# 4-20mA_Converter.net
KiCad netlist of a schematic drawn in Altium Designer
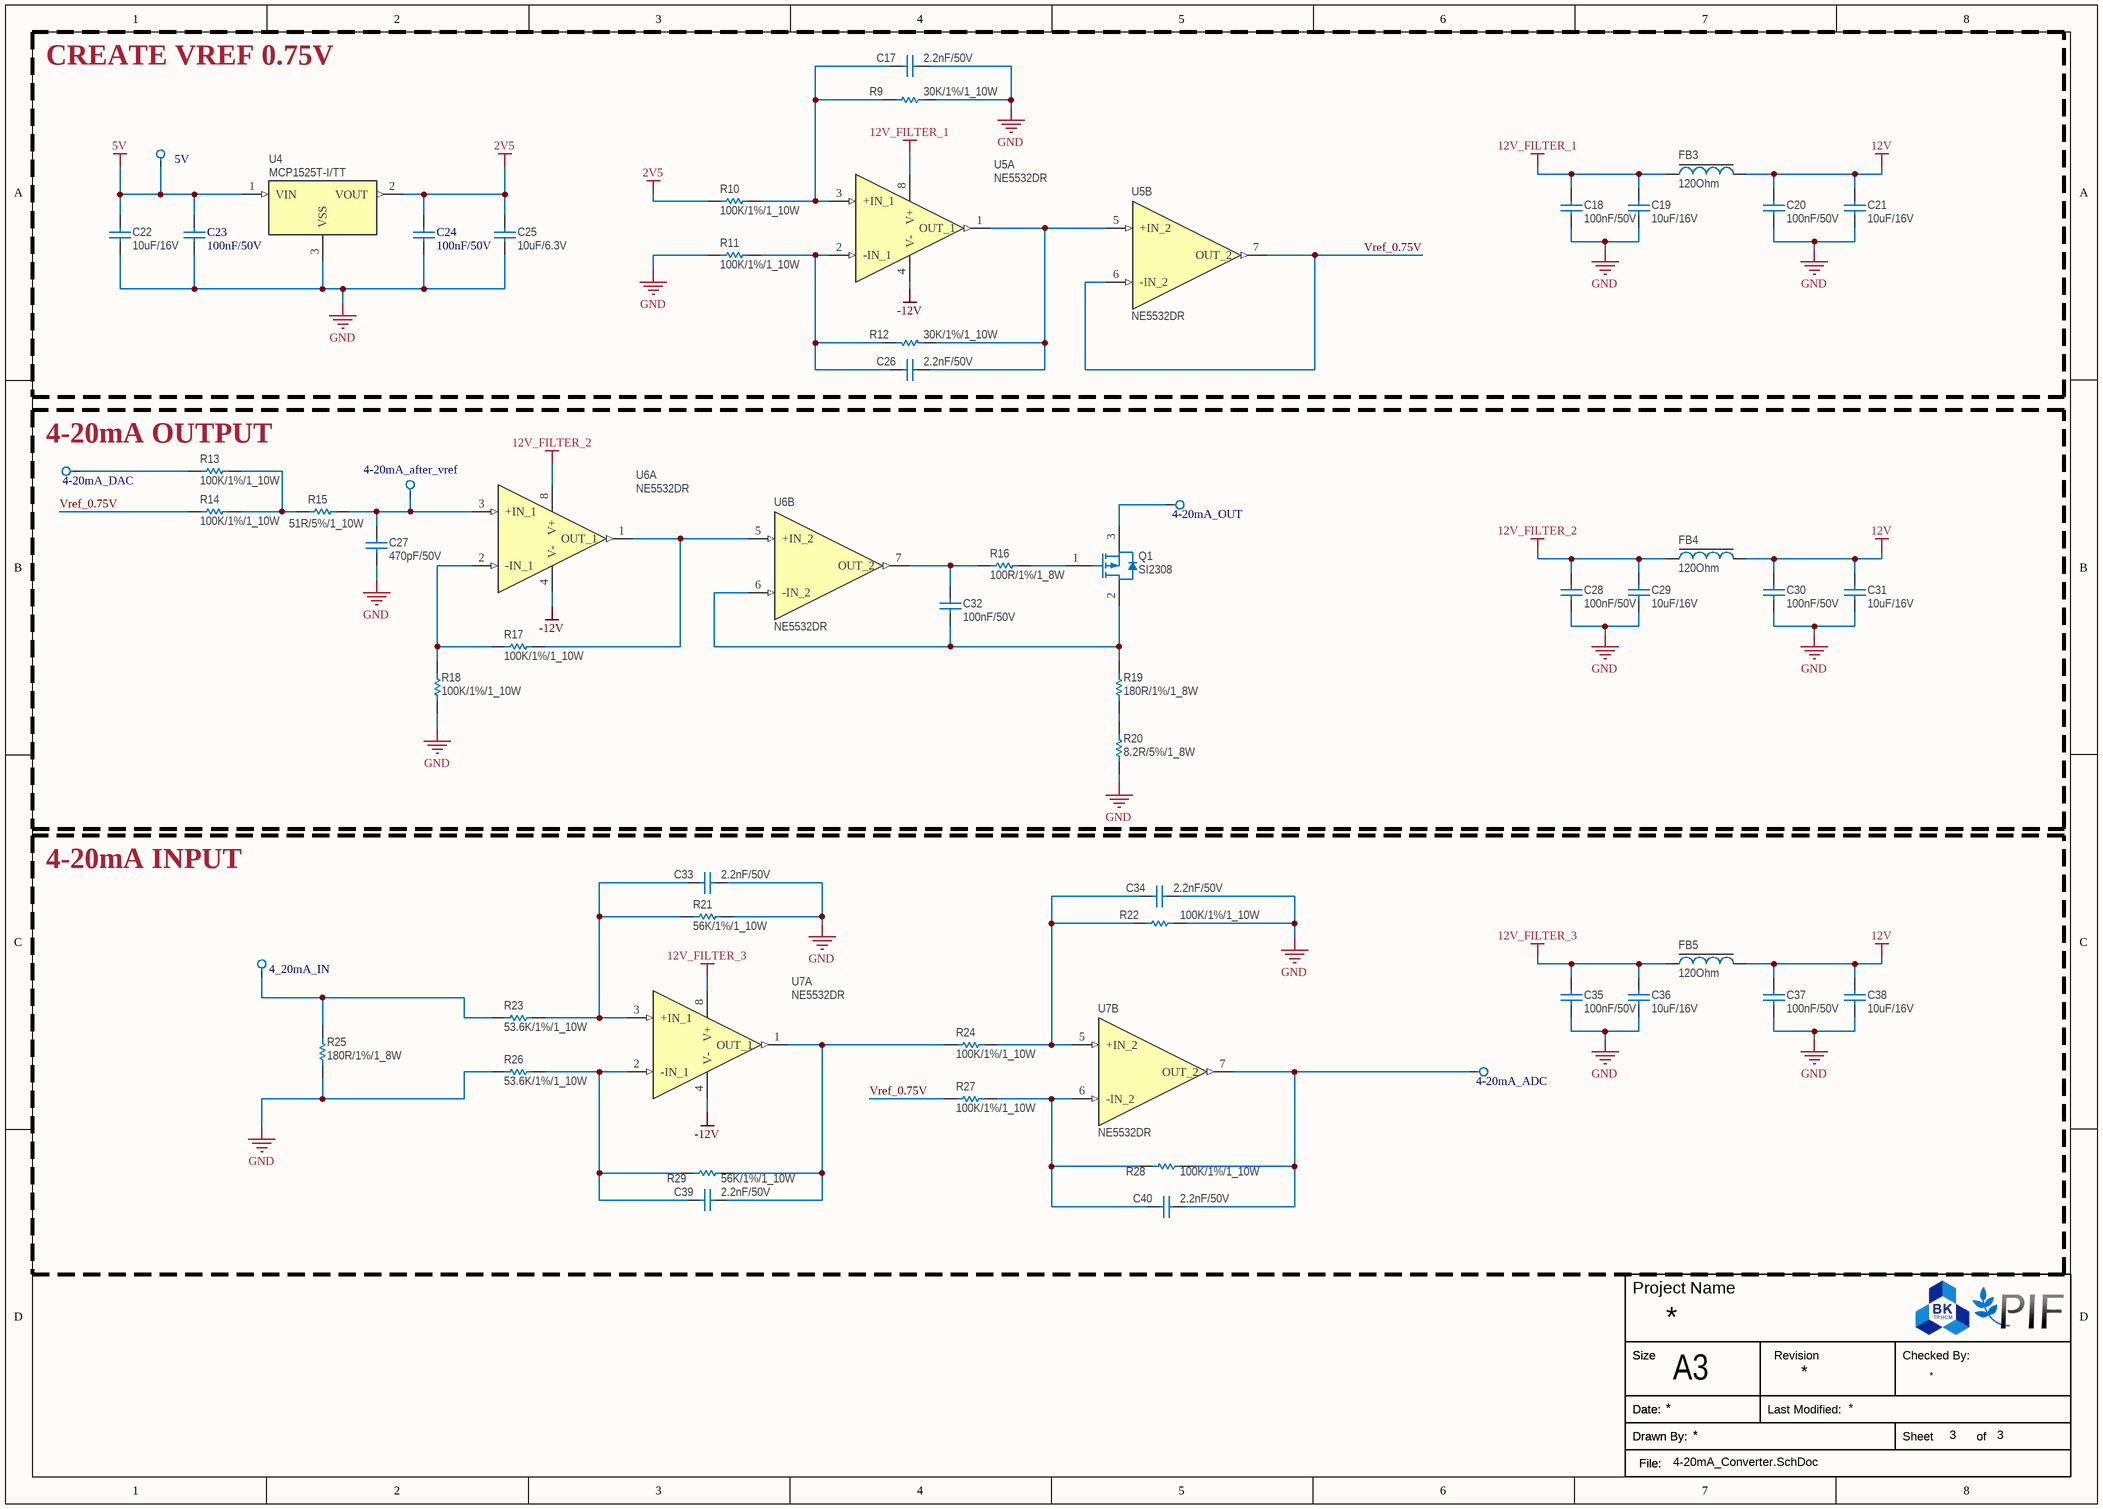
[diagram p0: 4-20mA_Converter.SchDoc]

(export (version "E")
  (design (tool "Eeschema 10.0.6"))
  (components
    (comp (ref "4-20mA_ADC")
      (value "4-20mA_ADC")
      (footprint "TestPoint_THTPad_D1.5mm_Drill0.7mm")
      (description "Test Point TEST-1BK")
      (libsource (lib "BluetoothTracking") (part "Testpoint_TH"))
    )
    (comp (ref "4-20mA_after_vref")
      (value "4-20mA_after_vref")
      (footprint "TestPoint_THTPad_D1.5mm_Drill0.7mm")
      (description "Test Point TEST-1BK")
      (libsource (lib "BluetoothTracking") (part "Testpoint_TH"))
    )
    (comp (ref "4-20mA_DAC")
      (value "4-20mA_DAC")
      (footprint "TestPoint_THTPad_D1.5mm_Drill0.7mm")
      (description "Test Point TEST-1BK")
      (libsource (lib "BluetoothTracking") (part "Testpoint_TH"))
    )
    (comp (ref "4-20mA_OUT")
      (value "4-20mA_OUT")
      (footprint "TestPoint_THTPad_D1.5mm_Drill0.7mm")
      (description "Test Point TEST-1BK")
      (libsource (lib "BluetoothTracking") (part "Testpoint_TH"))
    )
    (comp (ref "4_20mA_IN")
      (value "4_20mA_IN")
      (footprint "TestPoint_THTPad_D1.5mm_Drill0.7mm")
      (description "Test Point TEST-1BK")
      (libsource (lib "BluetoothTracking") (part "Testpoint_TH"))
    )
    (comp (ref "5V")
      (value "Testpoint_SMD")
      (footprint "TestPoint_Pad_3.0x3.0mm")
      (libsource (lib "BluetoothTracking") (part "Testpoint_SMD"))
    )
    (comp (ref "C17")
      (value "2.2nF/50V")
      (footprint "CAP_0603")
      (description "CAP, size 0603, 2.2nF, 50V")
      (fields (field (name "SUPPLY PART NUMBER") "CC0603KRX7R9BB222"))
      (libsource (lib "BluetoothTracking") (part "Ceramic_Cap_2.2nF_50V_0603"))
    )
    (comp (ref "C18")
      (value "100nF/50V")
      (footprint "CAP_0603")
      (description "CAP, size 0603, 100nF, 50V")
      (fields (field (name "SUPPLY PART NUMBER") "Tụ Gốm 0603 100nF (0.1uF) 50V"))
      (libsource (lib "BluetoothTracking") (part "Ceramic_Cap_100nF_50V_0603"))
    )
    (comp (ref "C19")
      (value "10uF/16V")
      (footprint "CAP_0603")
      (description "CAP, size 0603, 10uF, 16V")
      (fields (field (name "SUPPLY PART NUMBER") "Tụ Gốm 0603 10uF 16V"))
      (libsource (lib "BluetoothTracking") (part "Ceramic_Cap_10uF_16V_0603"))
    )
    (comp (ref "C20")
      (value "100nF/50V")
      (footprint "CAP_0603")
      (description "CAP, size 0603, 100nF, 50V")
      (fields (field (name "SUPPLY PART NUMBER") "Tụ Gốm 0603 100nF (0.1uF) 50V"))
      (libsource (lib "BluetoothTracking") (part "Ceramic_Cap_100nF_50V_0603"))
    )
    (comp (ref "C21")
      (value "10uF/16V")
      (footprint "CAP_0603")
      (description "CAP, size 0603, 10uF, 16V")
      (fields (field (name "SUPPLY PART NUMBER") "Tụ Gốm 0603 10uF 16V"))
      (libsource (lib "BluetoothTracking") (part "Ceramic_Cap_10uF_16V_0603"))
    )
    (comp (ref "C22")
      (value "10uF/16V")
      (footprint "CAP_0603")
      (description "CAP, size 0603, 10uF, 16V")
      (fields (field (name "SUPPLY PART NUMBER") "Tụ Gốm 0603 10uF 16V"))
      (libsource (lib "BluetoothTracking") (part "Ceramic_Cap_10uF_16V_0603"))
    )
    (comp (ref "C23")
      (value "100nF/50V")
      (footprint "CAP_0603")
      (description "CAP, size 0603, 100nF, 50V")
      (fields (field (name "SUPPLY PART NUMBER") "Tụ Gốm 0603 100nF (0.1uF) 50V"))
      (libsource (lib "BluetoothTracking") (part "Ceramic_Cap_100nF_50V_0603"))
    )
    (comp (ref "C24")
      (value "100nF/50V")
      (footprint "CAP_0603")
      (description "CAP, size 0603, 100nF, 50V")
      (fields (field (name "SUPPLY PART NUMBER") "Tụ Gốm 0603 100nF (0.1uF) 50V"))
      (libsource (lib "BluetoothTracking") (part "Ceramic_Cap_100nF_50V_0603"))
    )
    (comp (ref "C25")
      (value "10uF/6.3V")
      (footprint "CAP_0603")
      (description "CAP, size 0603, 10uF, 6.3V")
      (fields (field (name "SUPPLY PART NUMBER") "CC0603KRX5R5BB106"))
      (libsource (lib "BluetoothTracking") (part "Ceramic_Cap_10uF_6.3V_0603"))
    )
    (comp (ref "C26")
      (value "2.2nF/50V")
      (footprint "CAP_0603")
      (description "CAP, size 0603, 2.2nF, 50V")
      (fields (field (name "SUPPLY PART NUMBER") "CC0603KRX7R9BB222"))
      (libsource (lib "BluetoothTracking") (part "Ceramic_Cap_2.2nF_50V_0603"))
    )
    (comp (ref "C27")
      (value "470pF/50V")
      (footprint "CAP_0603")
      (description "CAP, size 0603, 470pF, 50V")
      (fields (field (name "SUPPLY PART NUMBER") "Tụ Gốm 0603 470pF 50V"))
      (libsource (lib "BluetoothTracking") (part "Ceramic_Cap_470pF_50V_0603"))
    )
    (comp (ref "C28")
      (value "100nF/50V")
      (footprint "CAP_0603")
      (description "CAP, size 0603, 100nF, 50V")
      (fields (field (name "SUPPLY PART NUMBER") "Tụ Gốm 0603 100nF (0.1uF) 50V"))
      (libsource (lib "BluetoothTracking") (part "Ceramic_Cap_100nF_50V_0603"))
    )
    (comp (ref "C29")
      (value "10uF/16V")
      (footprint "CAP_0603")
      (description "CAP, size 0603, 10uF, 16V")
      (fields (field (name "SUPPLY PART NUMBER") "Tụ Gốm 0603 10uF 16V"))
      (libsource (lib "BluetoothTracking") (part "Ceramic_Cap_10uF_16V_0603"))
    )
    (comp (ref "C30")
      (value "100nF/50V")
      (footprint "CAP_0603")
      (description "CAP, size 0603, 100nF, 50V")
      (fields (field (name "SUPPLY PART NUMBER") "Tụ Gốm 0603 100nF (0.1uF) 50V"))
      (libsource (lib "BluetoothTracking") (part "Ceramic_Cap_100nF_50V_0603"))
    )
    (comp (ref "C31")
      (value "10uF/16V")
      (footprint "CAP_0603")
      (description "CAP, size 0603, 10uF, 16V")
      (fields (field (name "SUPPLY PART NUMBER") "Tụ Gốm 0603 10uF 16V"))
      (libsource (lib "BluetoothTracking") (part "Ceramic_Cap_10uF_16V_0603"))
    )
    (comp (ref "C32")
      (value "100nF/50V")
      (footprint "CAP_0603")
      (description "CAP, size 0603, 100nF, 50V")
      (fields (field (name "SUPPLY PART NUMBER") "Tụ Gốm 0603 100nF (0.1uF) 50V"))
      (libsource (lib "BluetoothTracking") (part "Ceramic_Cap_100nF_50V_0603"))
    )
    (comp (ref "C33")
      (value "2.2nF/50V")
      (footprint "CAP_0603")
      (description "CAP, size 0603, 2.2nF, 50V")
      (fields (field (name "SUPPLY PART NUMBER") "CC0603KRX7R9BB222"))
      (libsource (lib "BluetoothTracking") (part "Ceramic_Cap_2.2nF_50V_0603"))
    )
    (comp (ref "C34")
      (value "2.2nF/50V")
      (footprint "CAP_0603")
      (description "CAP, size 0603, 2.2nF, 50V")
      (fields (field (name "SUPPLY PART NUMBER") "CC0603KRX7R9BB222"))
      (libsource (lib "BluetoothTracking") (part "Ceramic_Cap_2.2nF_50V_0603"))
    )
    (comp (ref "C35")
      (value "100nF/50V")
      (footprint "CAP_0603")
      (description "CAP, size 0603, 100nF, 50V")
      (fields (field (name "SUPPLY PART NUMBER") "Tụ Gốm 0603 100nF (0.1uF) 50V"))
      (libsource (lib "BluetoothTracking") (part "Ceramic_Cap_100nF_50V_0603"))
    )
    (comp (ref "C36")
      (value "10uF/16V")
      (footprint "CAP_0603")
      (description "CAP, size 0603, 10uF, 16V")
      (fields (field (name "SUPPLY PART NUMBER") "Tụ Gốm 0603 10uF 16V"))
      (libsource (lib "BluetoothTracking") (part "Ceramic_Cap_10uF_16V_0603"))
    )
    (comp (ref "C37")
      (value "100nF/50V")
      (footprint "CAP_0603")
      (description "CAP, size 0603, 100nF, 50V")
      (fields (field (name "SUPPLY PART NUMBER") "Tụ Gốm 0603 100nF (0.1uF) 50V"))
      (libsource (lib "BluetoothTracking") (part "Ceramic_Cap_100nF_50V_0603"))
    )
    (comp (ref "C38")
      (value "10uF/16V")
      (footprint "CAP_0603")
      (description "CAP, size 0603, 10uF, 16V")
      (fields (field (name "SUPPLY PART NUMBER") "Tụ Gốm 0603 10uF 16V"))
      (libsource (lib "BluetoothTracking") (part "Ceramic_Cap_10uF_16V_0603"))
    )
    (comp (ref "C39")
      (value "2.2nF/50V")
      (footprint "CAP_0603")
      (description "CAP, size 0603, 2.2nF, 50V")
      (fields (field (name "SUPPLY PART NUMBER") "CC0603KRX7R9BB222"))
      (libsource (lib "BluetoothTracking") (part "Ceramic_Cap_2.2nF_50V_0603"))
    )
    (comp (ref "C40")
      (value "2.2nF/50V")
      (footprint "CAP_0603")
      (description "CAP, size 0603, 2.2nF, 50V")
      (fields (field (name "SUPPLY PART NUMBER") "CC0603KRX7R9BB222"))
      (libsource (lib "BluetoothTracking") (part "Ceramic_Cap_2.2nF_50V_0603"))
    )
    (comp (ref "FB3")
      (value "120Ohm")
      (footprint "Ferrite_Bead_0805")
      (description "Ferrite Bead, size 0805, 120Ohm, 2A")
      (fields (field (name "SUPPLY PART NUMBER") "CBW201209U121T Ferrite Beads 2A 120 Ohm 0805"))
      (libsource (lib "BluetoothTracking") (part "Ferrite_Bead_120Ohm_2A_0805"))
    )
    (comp (ref "FB4")
      (value "120Ohm")
      (footprint "Ferrite_Bead_0805")
      (description "Ferrite Bead, size 0805, 120Ohm, 2A")
      (fields (field (name "SUPPLY PART NUMBER") "CBW201209U121T Ferrite Beads 2A 120 Ohm 0805"))
      (libsource (lib "BluetoothTracking") (part "Ferrite_Bead_120Ohm_2A_0805"))
    )
    (comp (ref "FB5")
      (value "120Ohm")
      (footprint "Ferrite_Bead_0805")
      (description "Ferrite Bead, size 0805, 120Ohm, 2A")
      (fields (field (name "SUPPLY PART NUMBER") "CBW201209U121T Ferrite Beads 2A 120 Ohm 0805"))
      (libsource (lib "BluetoothTracking") (part "Ferrite_Bead_120Ohm_2A_0805"))
    )
    (comp (ref "Q1")
      (value "SI2308")
      (footprint "SOT-23")
      (description "SI2308 SOT23 MOSFET N-CH 2A 60V")
      (libsource (lib "BluetoothTracking") (part "SI2308"))
    )
    (comp (ref "R9")
      (value "30K/1%/1_10W")
      (footprint "Resistor_0603")
      (description "Resistor 0603 30KOhm 1% 1_10W")
      (fields (field (name "SUPPLY PART NUMBER") "Điện Trở 30 KOhm 0603 1%"))
      (libsource (lib "BluetoothTracking") (part "Res_30K_0603_1%"))
    )
    (comp (ref "R10")
      (value "100K/1%/1_10W")
      (footprint "Resistor_0603")
      (description "Resistor 0603 100KOhm 1% 1_10W")
      (fields (field (name "SUPPLY PART NUMBER") "Điện Trở 100 KOhm 0603 1%"))
      (libsource (lib "BluetoothTracking") (part "Res_100K_0603_1%"))
    )
    (comp (ref "R11")
      (value "100K/1%/1_10W")
      (footprint "Resistor_0603")
      (description "Resistor 0603 100KOhm 1% 1_10W")
      (fields (field (name "SUPPLY PART NUMBER") "Điện Trở 100 KOhm 0603 1%"))
      (libsource (lib "BluetoothTracking") (part "Res_100K_0603_1%"))
    )
    (comp (ref "R12")
      (value "30K/1%/1_10W")
      (footprint "Resistor_0603")
      (description "Resistor 0603 30KOhm 1% 1_10W")
      (fields (field (name "SUPPLY PART NUMBER") "Điện Trở 30 KOhm 0603 1%"))
      (libsource (lib "BluetoothTracking") (part "Res_30K_0603_1%"))
    )
    (comp (ref "R13")
      (value "100K/1%/1_10W")
      (footprint "Resistor_0603")
      (description "Resistor 0603 100KOhm 1% 1_10W")
      (fields (field (name "SUPPLY PART NUMBER") "Điện Trở 100 KOhm 0603 1%"))
      (libsource (lib "BluetoothTracking") (part "Res_100K_0603_1%"))
    )
    (comp (ref "R14")
      (value "100K/1%/1_10W")
      (footprint "Resistor_0603")
      (description "Resistor 0603 100KOhm 1% 1_10W")
      (fields (field (name "SUPPLY PART NUMBER") "Điện Trở 100 KOhm 0603 1%"))
      (libsource (lib "BluetoothTracking") (part "Res_100K_0603_1%"))
    )
    (comp (ref "R15")
      (value "51R/5%/1_10W")
      (footprint "Resistor_0603")
      (description "Resistor 0603 51 Ohm 5% 1_10W")
      (fields (field (name "SUPPLY PART NUMBER") "Điện Trở 51 Ohm 0603 5%"))
      (libsource (lib "BluetoothTracking") (part "Res_51R_0603_5%"))
    )
    (comp (ref "R16")
      (value "100R/1%/1_8W")
      (footprint "Resistor_0603")
      (description "Resistor 0805 100 Ohm 1% 1_8W")
      (fields (field (name "SUPPLY PART NUMBER") "Điện Trở 100 Ohm 0805 1%"))
      (libsource (lib "BluetoothTracking") (part "Res_100R_0805_1%"))
    )
    (comp (ref "R17")
      (value "100K/1%/1_10W")
      (footprint "Resistor_0603")
      (description "Resistor 0603 100KOhm 1% 1_10W")
      (fields (field (name "SUPPLY PART NUMBER") "Điện Trở 100 KOhm 0603 1%"))
      (libsource (lib "BluetoothTracking") (part "Res_100K_0603_1%"))
    )
    (comp (ref "R18")
      (value "100K/1%/1_10W")
      (footprint "Resistor_0603")
      (description "Resistor 0603 100KOhm 1% 1_10W")
      (fields (field (name "SUPPLY PART NUMBER") "Điện Trở 100 KOhm 0603 1%"))
      (libsource (lib "BluetoothTracking") (part "Res_100K_0603_1%"))
    )
    (comp (ref "R19")
      (value "180R/1%/1_8W")
      (footprint "Resistor_0805")
      (description "Resistor 0805 180 Ohm 1% 1_8W")
      (fields (field (name "SUPPLY PART NUMBER") "Điện Trở 180 Ohm 0805 1%"))
      (libsource (lib "BluetoothTracking") (part "Res_180R_0805_1%"))
    )
    (comp (ref "R20")
      (value "8.2R/5%/1_8W")
      (footprint "Resistor_0805")
      (description "Resistor 0805 8.2 Ohm 5% 1_8W")
      (fields (field (name "SUPPLY PART NUMBER") "Điện Trở 8.2 Ohm 0805 5%"))
      (libsource (lib "BluetoothTracking") (part "Res_8.2R_0805_5%"))
    )
    (comp (ref "R21")
      (value "56K/1%/1_10W")
      (footprint "Resistor_0603")
      (description "Resistor 0603 56KOhm 1% 1_10W")
      (fields (field (name "SUPPLY PART NUMBER") "Điện Trở 56 KOhm 0603 1%"))
      (libsource (lib "BluetoothTracking") (part "Res_56K_0603_1%"))
    )
    (comp (ref "R22")
      (value "100K/1%/1_10W")
      (footprint "Resistor_0603")
      (description "Resistor 0603 100KOhm 1% 1_10W")
      (fields (field (name "SUPPLY PART NUMBER") "Điện Trở 100 KOhm 0603 1%"))
      (libsource (lib "BluetoothTracking") (part "Res_100K_0603_1%"))
    )
    (comp (ref "R23")
      (value "53.6K/1%/1_10W")
      (footprint "Resistor_0603")
      (description "Resistor 0603 53.6KOhm 1% 1_10W")
      (fields (field (name "SUPPLY PART NUMBER") "Điện Trở 53.6 KOhm 0603 1%"))
      (libsource (lib "BluetoothTracking") (part "Res_53.6K_0603_1%"))
    )
    (comp (ref "R24")
      (value "100K/1%/1_10W")
      (footprint "Resistor_0603")
      (description "Resistor 0603 100KOhm 1% 1_10W")
      (fields (field (name "SUPPLY PART NUMBER") "Điện Trở 100 KOhm 0603 1%"))
      (libsource (lib "BluetoothTracking") (part "Res_100K_0603_1%"))
    )
    (comp (ref "R25")
      (value "180R/1%/1_8W")
      (footprint "Resistor_0805")
      (description "Resistor 0805 180 Ohm 1% 1_8W")
      (fields (field (name "SUPPLY PART NUMBER") "Điện Trở 180 Ohm 0805 1%"))
      (libsource (lib "BluetoothTracking") (part "Res_180R_0805_1%"))
    )
    (comp (ref "R26")
      (value "53.6K/1%/1_10W")
      (footprint "Resistor_0603")
      (description "Resistor 0603 53.6KOhm 1% 1_10W")
      (fields (field (name "SUPPLY PART NUMBER") "Điện Trở 53.6 KOhm 0603 1%"))
      (libsource (lib "BluetoothTracking") (part "Res_53.6K_0603_1%"))
    )
    (comp (ref "R27")
      (value "100K/1%/1_10W")
      (footprint "Resistor_0603")
      (description "Resistor 0603 100KOhm 1% 1_10W")
      (fields (field (name "SUPPLY PART NUMBER") "Điện Trở 100 KOhm 0603 1%"))
      (libsource (lib "BluetoothTracking") (part "Res_100K_0603_1%"))
    )
    (comp (ref "R28")
      (value "100K/1%/1_10W")
      (footprint "Resistor_0603")
      (description "Resistor 0603 100KOhm 1% 1_10W")
      (fields (field (name "SUPPLY PART NUMBER") "Điện Trở 100 KOhm 0603 1%"))
      (libsource (lib "BluetoothTracking") (part "Res_100K_0603_1%"))
    )
    (comp (ref "R29")
      (value "56K/1%/1_10W")
      (footprint "Resistor_0603")
      (description "Resistor 0603 56KOhm 1% 1_10W")
      (fields (field (name "SUPPLY PART NUMBER") "Điện Trở 56 KOhm 0603 1%"))
      (libsource (lib "BluetoothTracking") (part "Res_56K_0603_1%"))
    )
    (comp (ref "U4")
      (value "MCP1525T-I/TT")
      (footprint "SOT-23")
      (description "Voltage Reference IC 2.5V")
      (fields (field (name "SUPPLY PART NUMBER") "MCP1525T-I/TT IC Tham Chiếu Điện Áp 2.5V SOT-23"))
      (libsource (lib "BluetoothTracking") (part "MCP1525T-I/TT"))
    )
    (comp (ref "U5")
      (value "NE5532DR")
      (footprint "SOIC-8")
      (description "Low Noise Single/Dual Operational Amplifier - SOIC-8")
      (libsource (lib "BluetoothTracking") (part "NE5532DR"))
    )
    (comp (ref "U6")
      (value "NE5532DR")
      (footprint "SOIC-8")
      (description "Low Noise Single/Dual Operational Amplifier - SOIC-8")
      (libsource (lib "BluetoothTracking") (part "NE5532DR"))
    )
    (comp (ref "U7")
      (value "NE5532DR")
      (footprint "SOIC-8")
      (description "Low Noise Single/Dual Operational Amplifier - SOIC-8")
      (libsource (lib "BluetoothTracking") (part "NE5532DR"))
    )
  )
  (nets
    (net (code "1") (name "-12V") (class "Default")
      (node (ref "U5") (pin "4") (pinfunction "V-_4") (pintype "power_in"))
      (node (ref "U6") (pin "4") (pinfunction "V-_4") (pintype "power_in"))
      (node (ref "U7") (pin "4") (pinfunction "V-_4") (pintype "power_in"))
    )
    (net (code "2") (name "/Vref_0.75V") (class "Default")
      (node (ref "R14") (pin "1") (pinfunction "1_1") (pintype "passive"))
      (node (ref "R27") (pin "1") (pinfunction "1_1") (pintype "passive"))
      (node (ref "U5") (pin "6") (pinfunction "-IN_2_6") (pintype "input"))
      (node (ref "U5") (pin "7") (pinfunction "OUT_2_7") (pintype "output"))
    )
    (net (code "3") (name "2V5") (class "Default")
      (node (ref "C24") (pin "2") (pinfunction "2_2") (pintype "passive"))
      (node (ref "C25") (pin "2") (pinfunction "2_2") (pintype "passive"))
      (node (ref "R10") (pin "1") (pinfunction "1_1") (pintype "passive"))
      (node (ref "U4") (pin "2") (pinfunction "VOUT_2") (pintype "output"))
    )
    (net (code "4") (name "5V") (class "Default")
      (node (ref "5V") (pin "1") (pinfunction "1_1") (pintype "passive"))
      (node (ref "C22") (pin "2") (pinfunction "2_2") (pintype "passive"))
      (node (ref "C23") (pin "2") (pinfunction "2_2") (pintype "passive"))
      (node (ref "U4") (pin "1") (pinfunction "VIN_1") (pintype "input"))
    )
    (net (code "5") (name "12V") (class "Default")
      (node (ref "C20") (pin "2") (pinfunction "2_2") (pintype "passive"))
      (node (ref "C21") (pin "2") (pinfunction "2_2") (pintype "passive"))
      (node (ref "C30") (pin "2") (pinfunction "2_2") (pintype "passive"))
      (node (ref "C31") (pin "2") (pinfunction "2_2") (pintype "passive"))
      (node (ref "C37") (pin "2") (pinfunction "2_2") (pintype "passive"))
      (node (ref "C38") (pin "2") (pinfunction "2_2") (pintype "passive"))
      (node (ref "FB3") (pin "2") (pinfunction "2_2") (pintype "passive"))
      (node (ref "FB4") (pin "2") (pinfunction "2_2") (pintype "passive"))
      (node (ref "FB5") (pin "2") (pinfunction "2_2") (pintype "passive"))
    )
    (net (code "6") (name "12V_FILTER_1") (class "Default")
      (node (ref "C18") (pin "2") (pinfunction "2_2") (pintype "passive"))
      (node (ref "C19") (pin "2") (pinfunction "2_2") (pintype "passive"))
      (node (ref "FB3") (pin "1") (pinfunction "1_1") (pintype "passive"))
      (node (ref "U5") (pin "8") (pinfunction "V+_8") (pintype "power_in"))
    )
    (net (code "7") (name "12V_FILTER_2") (class "Default")
      (node (ref "C28") (pin "2") (pinfunction "2_2") (pintype "passive"))
      (node (ref "C29") (pin "2") (pinfunction "2_2") (pintype "passive"))
      (node (ref "FB4") (pin "1") (pinfunction "1_1") (pintype "passive"))
      (node (ref "U6") (pin "8") (pinfunction "V+_8") (pintype "power_in"))
    )
    (net (code "8") (name "12V_FILTER_3") (class "Default")
      (node (ref "C35") (pin "2") (pinfunction "2_2") (pintype "passive"))
      (node (ref "C36") (pin "2") (pinfunction "2_2") (pintype "passive"))
      (node (ref "FB5") (pin "1") (pinfunction "1_1") (pintype "passive"))
      (node (ref "U7") (pin "8") (pinfunction "V+_8") (pintype "power_in"))
    )
    (net (code "9") (name "GND") (class "Default")
      (node (ref "C17") (pin "2") (pinfunction "2_2") (pintype "passive"))
      (node (ref "C18") (pin "1") (pinfunction "1_1") (pintype "passive"))
      (node (ref "C19") (pin "1") (pinfunction "1_1") (pintype "passive"))
      (node (ref "C20") (pin "1") (pinfunction "1_1") (pintype "passive"))
      (node (ref "C21") (pin "1") (pinfunction "1_1") (pintype "passive"))
      (node (ref "C22") (pin "1") (pinfunction "1_1") (pintype "passive"))
      (node (ref "C23") (pin "1") (pinfunction "1_1") (pintype "passive"))
      (node (ref "C24") (pin "1") (pinfunction "1_1") (pintype "passive"))
      (node (ref "C25") (pin "1") (pinfunction "1_1") (pintype "passive"))
      (node (ref "C27") (pin "1") (pinfunction "1_1") (pintype "passive"))
      (node (ref "C28") (pin "1") (pinfunction "1_1") (pintype "passive"))
      (node (ref "C29") (pin "1") (pinfunction "1_1") (pintype "passive"))
      (node (ref "C30") (pin "1") (pinfunction "1_1") (pintype "passive"))
      (node (ref "C31") (pin "1") (pinfunction "1_1") (pintype "passive"))
      (node (ref "C33") (pin "2") (pinfunction "2_2") (pintype "passive"))
      (node (ref "C34") (pin "2") (pinfunction "2_2") (pintype "passive"))
      (node (ref "C35") (pin "1") (pinfunction "1_1") (pintype "passive"))
      (node (ref "C36") (pin "1") (pinfunction "1_1") (pintype "passive"))
      (node (ref "C37") (pin "1") (pinfunction "1_1") (pintype "passive"))
      (node (ref "C38") (pin "1") (pinfunction "1_1") (pintype "passive"))
      (node (ref "R11") (pin "1") (pinfunction "1_1") (pintype "passive"))
      (node (ref "R18") (pin "1") (pinfunction "1_1") (pintype "passive"))
      (node (ref "R20") (pin "2") (pinfunction "2_2") (pintype "passive"))
      (node (ref "R21") (pin "2") (pinfunction "2_2") (pintype "passive"))
      (node (ref "R22") (pin "2") (pinfunction "2_2") (pintype "passive"))
      (node (ref "R25") (pin "1") (pinfunction "1_1") (pintype "passive"))
      (node (ref "R26") (pin "1") (pinfunction "1_1") (pintype "passive"))
      (node (ref "R9") (pin "2") (pinfunction "2_2") (pintype "passive"))
      (node (ref "U4") (pin "3") (pinfunction "VSS_3") (pintype "passive"))
    )
    (net (code "10") (name "Net-(4-20mA_DAC-Pad1)") (class "Default")
      (node (ref "4-20mA_DAC") (pin "1") (pinfunction "1_1") (pintype "passive"))
      (node (ref "R13") (pin "1") (pinfunction "1_1") (pintype "passive"))
    )
    (net (code "11") (name "Net-(4_20mA_IN-Pad1)") (class "Default")
      (node (ref "4_20mA_IN") (pin "1") (pinfunction "1_1") (pintype "passive"))
      (node (ref "R23") (pin "1") (pinfunction "1_1") (pintype "passive"))
      (node (ref "R25") (pin "2") (pinfunction "2_2") (pintype "passive"))
    )
    (net (code "12") (name "Net-(Q1-DRAIN)") (class "Default")
      (node (ref "4-20mA_OUT") (pin "1") (pinfunction "1_1") (pintype "passive"))
      (node (ref "Q1") (pin "3") (pinfunction "DRAIN_3") (pintype "passive"))
    )
    (net (code "13") (name "Net-(Q1-GATE)") (class "Default")
      (node (ref "Q1") (pin "1") (pinfunction "GATE_1") (pintype "passive"))
      (node (ref "R16") (pin "2") (pinfunction "2_2") (pintype "passive"))
    )
    (net (code "14") (name "Net-(Q1-SOURCE)") (class "Default")
      (node (ref "C32") (pin "1") (pinfunction "1_1") (pintype "passive"))
      (node (ref "Q1") (pin "2") (pinfunction "SOURCE_2") (pintype "passive"))
      (node (ref "R19") (pin "2") (pinfunction "2_2") (pintype "passive"))
      (node (ref "U6") (pin "6") (pinfunction "-IN_2_6") (pintype "input"))
    )
    (net (code "15") (name "Net-(R13-Pad2)") (class "Default")
      (node (ref "R13") (pin "2") (pinfunction "2_2") (pintype "passive"))
      (node (ref "R14") (pin "2") (pinfunction "2_2") (pintype "passive"))
      (node (ref "R15") (pin "1") (pinfunction "1_1") (pintype "passive"))
    )
    (net (code "16") (name "Net-(R19-Pad1)") (class "Default")
      (node (ref "R19") (pin "1") (pinfunction "1_1") (pintype "passive"))
      (node (ref "R20") (pin "1") (pinfunction "1_1") (pintype "passive"))
    )
    (net (code "17") (name "Net-(U5A-+IN_1)") (class "Default")
      (node (ref "C17") (pin "1") (pinfunction "1_1") (pintype "passive"))
      (node (ref "R10") (pin "2") (pinfunction "2_2") (pintype "passive"))
      (node (ref "R9") (pin "1") (pinfunction "1_1") (pintype "passive"))
      (node (ref "U5") (pin "3") (pinfunction "+IN_1_3") (pintype "input"))
    )
    (net (code "18") (name "Net-(U5A--IN_1)") (class "Default")
      (node (ref "C26") (pin "1") (pinfunction "1_1") (pintype "passive"))
      (node (ref "R11") (pin "2") (pinfunction "2_2") (pintype "passive"))
      (node (ref "R12") (pin "1") (pinfunction "1_1") (pintype "passive"))
      (node (ref "U5") (pin "2") (pinfunction "-IN_1_2") (pintype "input"))
    )
    (net (code "19") (name "Net-(U5A-OUT_1)") (class "Default")
      (node (ref "C26") (pin "2") (pinfunction "2_2") (pintype "passive"))
      (node (ref "R12") (pin "2") (pinfunction "2_2") (pintype "passive"))
      (node (ref "U5") (pin "1") (pinfunction "OUT_1_1") (pintype "output"))
      (node (ref "U5") (pin "5") (pinfunction "+IN_2_5") (pintype "input"))
    )
    (net (code "20") (name "Net-(U6A-+IN_1)") (class "Default")
      (node (ref "4-20mA_after_vref") (pin "1") (pinfunction "1_1") (pintype "passive"))
      (node (ref "C27") (pin "2") (pinfunction "2_2") (pintype "passive"))
      (node (ref "R15") (pin "2") (pinfunction "2_2") (pintype "passive"))
      (node (ref "U6") (pin "3") (pinfunction "+IN_1_3") (pintype "input"))
    )
    (net (code "21") (name "Net-(U6A--IN_1)") (class "Default")
      (node (ref "R17") (pin "1") (pinfunction "1_1") (pintype "passive"))
      (node (ref "R18") (pin "2") (pinfunction "2_2") (pintype "passive"))
      (node (ref "U6") (pin "2") (pinfunction "-IN_1_2") (pintype "input"))
    )
    (net (code "22") (name "Net-(U6A-OUT_1)") (class "Default")
      (node (ref "R17") (pin "2") (pinfunction "2_2") (pintype "passive"))
      (node (ref "U6") (pin "1") (pinfunction "OUT_1_1") (pintype "output"))
      (node (ref "U6") (pin "5") (pinfunction "+IN_2_5") (pintype "input"))
    )
    (net (code "23") (name "Net-(U6B-OUT_2)") (class "Default")
      (node (ref "C32") (pin "2") (pinfunction "2_2") (pintype "passive"))
      (node (ref "R16") (pin "1") (pinfunction "1_1") (pintype "passive"))
      (node (ref "U6") (pin "7") (pinfunction "OUT_2_7") (pintype "output"))
    )
    (net (code "24") (name "Net-(U7A-+IN_1)") (class "Default")
      (node (ref "C33") (pin "1") (pinfunction "1_1") (pintype "passive"))
      (node (ref "R21") (pin "1") (pinfunction "1_1") (pintype "passive"))
      (node (ref "R23") (pin "2") (pinfunction "2_2") (pintype "passive"))
      (node (ref "U7") (pin "3") (pinfunction "+IN_1_3") (pintype "input"))
    )
    (net (code "25") (name "Net-(U7A--IN_1)") (class "Default")
      (node (ref "C39") (pin "1") (pinfunction "1_1") (pintype "passive"))
      (node (ref "R26") (pin "2") (pinfunction "2_2") (pintype "passive"))
      (node (ref "R29") (pin "1") (pinfunction "1_1") (pintype "passive"))
      (node (ref "U7") (pin "2") (pinfunction "-IN_1_2") (pintype "input"))
    )
    (net (code "26") (name "Net-(U7A-OUT_1)") (class "Default")
      (node (ref "C39") (pin "2") (pinfunction "2_2") (pintype "passive"))
      (node (ref "R24") (pin "1") (pinfunction "1_1") (pintype "passive"))
      (node (ref "R29") (pin "2") (pinfunction "2_2") (pintype "passive"))
      (node (ref "U7") (pin "1") (pinfunction "OUT_1_1") (pintype "output"))
    )
    (net (code "27") (name "Net-(U7B-+IN_2)") (class "Default")
      (node (ref "C34") (pin "1") (pinfunction "1_1") (pintype "passive"))
      (node (ref "R22") (pin "1") (pinfunction "1_1") (pintype "passive"))
      (node (ref "R24") (pin "2") (pinfunction "2_2") (pintype "passive"))
      (node (ref "U7") (pin "5") (pinfunction "+IN_2_5") (pintype "input"))
    )
    (net (code "28") (name "Net-(U7B--IN_2)") (class "Default")
      (node (ref "C40") (pin "1") (pinfunction "1_1") (pintype "passive"))
      (node (ref "R27") (pin "2") (pinfunction "2_2") (pintype "passive"))
      (node (ref "R28") (pin "1") (pinfunction "1_1") (pintype "passive"))
      (node (ref "U7") (pin "6") (pinfunction "-IN_2_6") (pintype "input"))
    )
    (net (code "29") (name "Net-(U7B-OUT_2)") (class "Default")
      (node (ref "4-20mA_ADC") (pin "1") (pinfunction "1_1") (pintype "passive"))
      (node (ref "C40") (pin "2") (pinfunction "2_2") (pintype "passive"))
      (node (ref "R28") (pin "2") (pinfunction "2_2") (pintype "passive"))
      (node (ref "U7") (pin "7") (pinfunction "OUT_2_7") (pintype "output"))
    )
  )
)
